# Reducteur_tension.net
KiCad netlist of a schematic drawn in Altium Designer
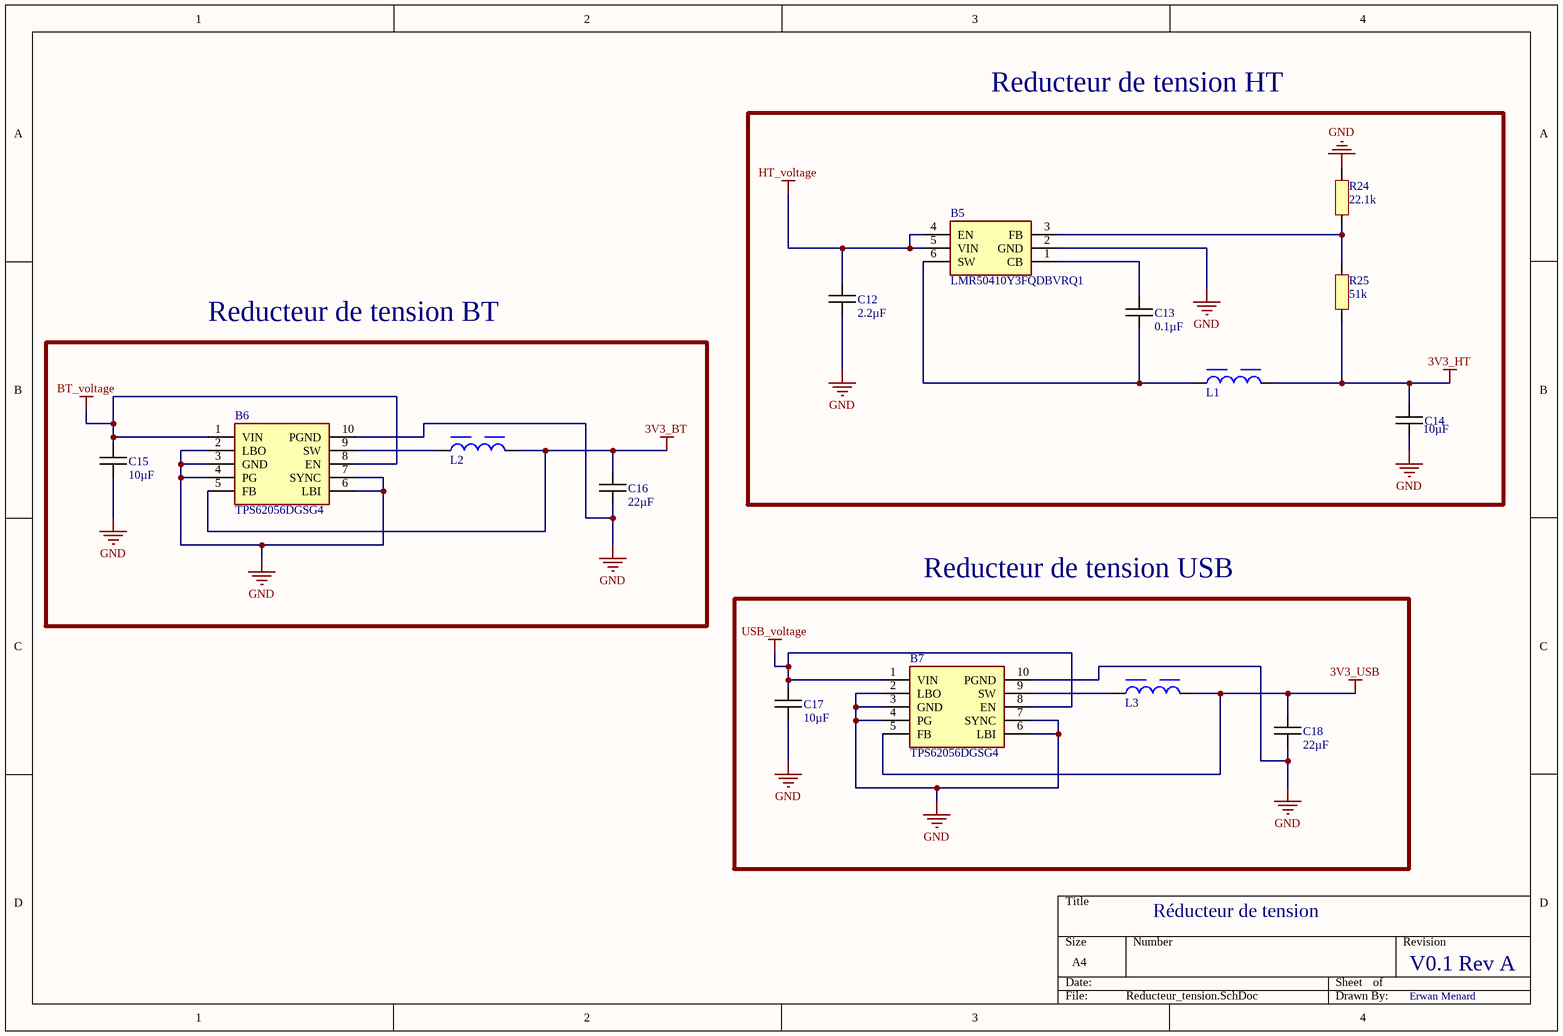
[diagram p0: Reducteur_tension.SchDoc]

(export (version "E")
  (design (tool "Eeschema 10.0.6"))
  (components
    (comp (ref "B5")
      (value "LMR50410Y3FQDBVRQ1")
      (footprint "SOT95P280X145-6N")
      (fields (field (name "MOUSER PART NUMBER") "595-R50410Y3FQDBVRQ1"))
      (libsource (lib "SCHLibrary") (part "LMR50410Y3FQDBVRQ1"))
    )
    (comp (ref "B6")
      (value "TPS62056DGSG4")
      (footprint "SOP50P490X110-10N")
      (fields (field (name "MOUSER PART NUMBER") "595-TPS62056DGSG4"))
      (libsource (lib "SCHLibrary") (part "TPS62056DGSG4"))
    )
    (comp (ref "B7")
      (value "TPS62056DGSG4")
      (footprint "SOP50P490X110-10N")
      (fields (field (name "MOUSER PART NUMBER") "595-TPS62056DGSG4"))
      (libsource (lib "SCHLibrary") (part "TPS62056DGSG4"))
    )
    (comp (ref "C12")
      (value "2.2µF")
      (footprint "CAPC1005X06N")
      (libsource (lib "SCHLibrary") (part "Capacitor"))
    )
    (comp (ref "C13")
      (value "0.1µF")
      (footprint "CAPC1005X06N")
      (libsource (lib "SCHLibrary") (part "Capacitor"))
    )
    (comp (ref "C14")
      (value "10µF")
      (footprint "CAPC1005X06N")
      (libsource (lib "SCHLibrary") (part "Capacitor"))
    )
    (comp (ref "C15")
      (value "10µF")
      (footprint "CAPC1005X06N")
      (libsource (lib "SCHLibrary") (part "Capacitor"))
    )
    (comp (ref "C16")
      (value "22µF")
      (footprint "CAPC1005X06N")
      (libsource (lib "SCHLibrary") (part "Capacitor"))
    )
    (comp (ref "C17")
      (value "10µF")
      (footprint "CAPC1005X06N")
      (libsource (lib "SCHLibrary") (part "Capacitor"))
    )
    (comp (ref "C18")
      (value "22µF")
      (footprint "CAPC1005X06N")
      (libsource (lib "SCHLibrary") (part "Capacitor"))
    )
    (comp (ref "L1")
      (value "3.3uH, 3.5A")
      (footprint "WE-LHMI_4020")
      (description "WE-LHMI SMT Power Inductor, size 4020, 3.3uH, 3.5A, 76mOhm")
      (fields
        (field (name "MANUFACTURER PART NUMBER") "74437324033")
        (field (name "MANUFACTURER") "Wurth Elektronik")
      )
      (libsource (lib "SCHLibrary") (part "74437324033"))
    )
    (comp (ref "L2")
      (value "10uH, 3.5A")
      (footprint "WE-LHMI_4020")
      (description "WE-LHMI SMT Power Inductor, size 4020, 3.3uH, 3.5A, 76mOhm")
      (fields
        (field (name "MANUFACTURER PART NUMBER") "74437324033")
        (field (name "MANUFACTURER") "Wurth Elektronik")
      )
      (libsource (lib "SCHLibrary") (part "74437324033"))
    )
    (comp (ref "L3")
      (value "10uH, 3.5A")
      (footprint "WE-LHMI_4020")
      (description "WE-LHMI SMT Power Inductor, size 4020, 3.3uH, 3.5A, 76mOhm")
      (fields
        (field (name "MANUFACTURER PART NUMBER") "74437324033")
        (field (name "MANUFACTURER") "Wurth Elektronik")
      )
      (libsource (lib "SCHLibrary") (part "74437324033"))
    )
    (comp (ref "R24")
      (value "22.1k")
      (footprint "RESC1005X06N")
      (libsource (lib "SCHLibrary") (part "Resistor"))
    )
    (comp (ref "R25")
      (value "51k")
      (footprint "RESC1005X06N")
      (libsource (lib "SCHLibrary") (part "Resistor"))
    )
  )
  (nets
    (net (code "1") (name "3V3_BT") (class "Default")
      (node (ref "B6") (pin "5") (pinfunction "FB_5") (pintype "passive"))
      (node (ref "C16") (pin "1") (pinfunction "1_1") (pintype "passive"))
      (node (ref "L2") (pin "2") (pinfunction "2_2") (pintype "passive"))
    )
    (net (code "2") (name "3V3_HT") (class "Default")
      (node (ref "C14") (pin "1") (pinfunction "1_1") (pintype "passive"))
      (node (ref "L1") (pin "2") (pinfunction "2_2") (pintype "passive"))
      (node (ref "R25") (pin "1") (pinfunction "1_1") (pintype "passive"))
    )
    (net (code "3") (name "3V3_USB") (class "Default")
      (node (ref "B7") (pin "5") (pinfunction "FB_5") (pintype "passive"))
      (node (ref "C18") (pin "1") (pinfunction "1_1") (pintype "passive"))
      (node (ref "L3") (pin "2") (pinfunction "2_2") (pintype "passive"))
    )
    (net (code "4") (name "BT_voltage") (class "Default")
      (node (ref "B6") (pin "1") (pinfunction "VIN_1") (pintype "passive"))
      (node (ref "B6") (pin "8") (pinfunction "EN_8") (pintype "passive"))
      (node (ref "C15") (pin "1") (pinfunction "1_1") (pintype "passive"))
    )
    (net (code "5") (name "GND") (class "Default")
      (node (ref "B5") (pin "2") (pinfunction "GND_2") (pintype "passive"))
      (node (ref "B6") (pin "10") (pinfunction "PGND_10") (pintype "passive"))
      (node (ref "B6") (pin "2") (pinfunction "LBO_2") (pintype "passive"))
      (node (ref "B6") (pin "3") (pinfunction "GND_3") (pintype "passive"))
      (node (ref "B6") (pin "4") (pinfunction "PG_4") (pintype "passive"))
      (node (ref "B6") (pin "6") (pinfunction "LBI_6") (pintype "passive"))
      (node (ref "B6") (pin "7") (pinfunction "SYNC_7") (pintype "passive"))
      (node (ref "B7") (pin "10") (pinfunction "PGND_10") (pintype "passive"))
      (node (ref "B7") (pin "2") (pinfunction "LBO_2") (pintype "passive"))
      (node (ref "B7") (pin "3") (pinfunction "GND_3") (pintype "passive"))
      (node (ref "B7") (pin "4") (pinfunction "PG_4") (pintype "passive"))
      (node (ref "B7") (pin "6") (pinfunction "LBI_6") (pintype "passive"))
      (node (ref "B7") (pin "7") (pinfunction "SYNC_7") (pintype "passive"))
      (node (ref "C12") (pin "2") (pinfunction "2_2") (pintype "passive"))
      (node (ref "C14") (pin "2") (pinfunction "2_2") (pintype "passive"))
      (node (ref "C15") (pin "2") (pinfunction "2_2") (pintype "passive"))
      (node (ref "C16") (pin "2") (pinfunction "2_2") (pintype "passive"))
      (node (ref "C17") (pin "2") (pinfunction "2_2") (pintype "passive"))
      (node (ref "C18") (pin "2") (pinfunction "2_2") (pintype "passive"))
      (node (ref "R24") (pin "2") (pinfunction "2_2") (pintype "passive"))
    )
    (net (code "6") (name "HT_voltage") (class "Default")
      (node (ref "B5") (pin "4") (pinfunction "EN_4") (pintype "passive"))
      (node (ref "B5") (pin "5") (pinfunction "VIN_5") (pintype "passive"))
      (node (ref "C12") (pin "1") (pinfunction "1_1") (pintype "passive"))
    )
    (net (code "7") (name "Net-(B5-CB)") (class "Default")
      (node (ref "B5") (pin "1") (pinfunction "CB_1") (pintype "passive"))
      (node (ref "C13") (pin "1") (pinfunction "1_1") (pintype "passive"))
    )
    (net (code "8") (name "Net-(B5-FB)") (class "Default")
      (node (ref "B5") (pin "3") (pinfunction "FB_3") (pintype "passive"))
      (node (ref "R24") (pin "1") (pinfunction "1_1") (pintype "passive"))
      (node (ref "R25") (pin "2") (pinfunction "2_2") (pintype "passive"))
    )
    (net (code "9") (name "Net-(B5-SW)") (class "Default")
      (node (ref "B5") (pin "6") (pinfunction "SW_6") (pintype "passive"))
      (node (ref "C13") (pin "2") (pinfunction "2_2") (pintype "passive"))
      (node (ref "L1") (pin "1") (pinfunction "1_1") (pintype "passive"))
    )
    (net (code "10") (name "Net-(B6-SW)") (class "Default")
      (node (ref "B6") (pin "9") (pinfunction "SW_9") (pintype "passive"))
      (node (ref "L2") (pin "1") (pinfunction "1_1") (pintype "passive"))
    )
    (net (code "11") (name "Net-(B7-SW)") (class "Default")
      (node (ref "B7") (pin "9") (pinfunction "SW_9") (pintype "passive"))
      (node (ref "L3") (pin "1") (pinfunction "1_1") (pintype "passive"))
    )
    (net (code "12") (name "USB_voltage") (class "Default")
      (node (ref "B7") (pin "1") (pinfunction "VIN_1") (pintype "passive"))
      (node (ref "B7") (pin "8") (pinfunction "EN_8") (pintype "passive"))
      (node (ref "C17") (pin "1") (pinfunction "1_1") (pintype "passive"))
    )
  )
)
